# Si570_USB.net
KiCad netlist of a schematic drawn in EAGLE
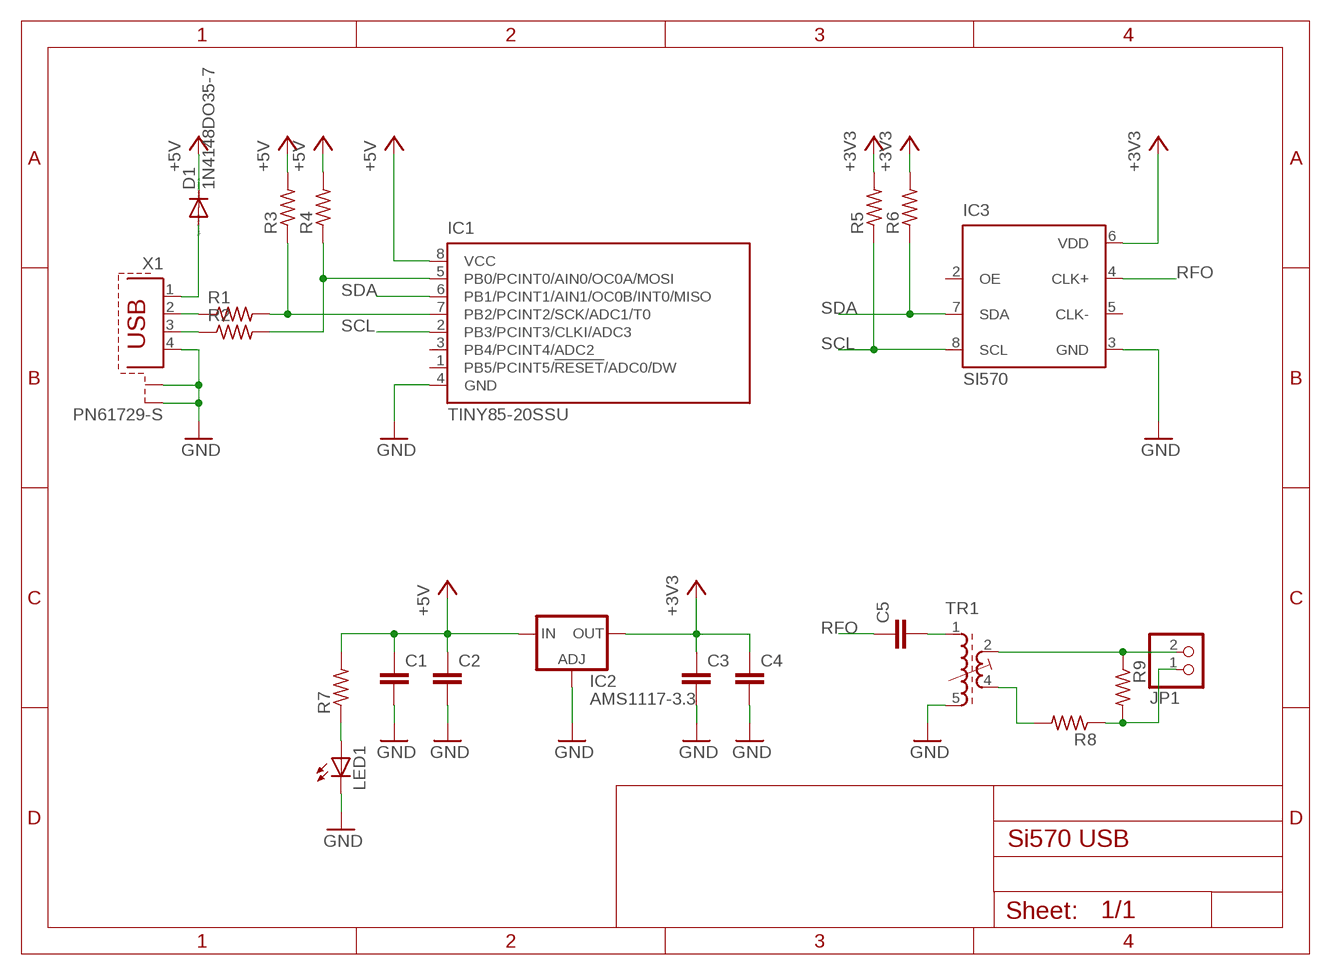
[diagram p0: schematic, sheet 1]

(export (version "E")
  (design (tool "Eeschema 10.0.6"))
  (components
    (comp (ref "C1")
      (value "C-EUC1206K")
      (footprint "eagle-import:C1206K")
      (libsource (lib "eagle-import") (part "C-EUC1206K"))
    )
    (comp (ref "C2")
      (value "C-EUC1206K")
      (footprint "eagle-import:C1206K")
      (libsource (lib "eagle-import") (part "C-EUC1206K"))
    )
    (comp (ref "C3")
      (value "C-EUC1206K")
      (footprint "eagle-import:C1206K")
      (libsource (lib "eagle-import") (part "C-EUC1206K"))
    )
    (comp (ref "C4")
      (value "C-EUC1206K")
      (footprint "eagle-import:C1206K")
      (libsource (lib "eagle-import") (part "C-EUC1206K"))
    )
    (comp (ref "C5")
      (value "C-EUC1206K")
      (footprint "eagle-import:C1206K")
      (libsource (lib "eagle-import") (part "C-EUC1206K"))
    )
    (comp (ref "D1")
      (value "1N4148DO35-7")
      (footprint "eagle-import:DO35-7")
      (libsource (lib "eagle-import") (part "1N4148DO35-7"))
    )
    (comp (ref "IC1")
      (value "TINY85-20SSU")
      (footprint "eagle-import:8S1")
      (fields (field (name "MPN") "ATTINY13-20SSU"))
      (libsource (lib "eagle-import") (part "TINY13SSU-20"))
    )
    (comp (ref "IC2")
      (value "AMS1117-3.3")
      (footprint "eagle-import:SOT223")
      (libsource (lib "eagle-import") (part "LD117A?S33TR"))
    )
    (comp (ref "IC3")
      (value "SI570")
      (footprint "eagle-import:8-PIN")
      (libsource (lib "eagle-import") (part "SI570"))
    )
    (comp (ref "JP1")
      (value "PINHD-1X2")
      (footprint "eagle-import:1X02")
      (libsource (lib "eagle-import") (part "PINHD-1X2"))
    )
    (comp (ref "LED1")
      (value "LED3MM")
      (footprint "eagle-import:LED3MM")
      (libsource (lib "eagle-import") (part "LED3MM"))
    )
    (comp (ref "R1")
      (value "R-US_R1206")
      (footprint "eagle-import:R1206")
      (libsource (lib "eagle-import") (part "R-US_R1206"))
    )
    (comp (ref "R2")
      (value "R-US_R1206")
      (footprint "eagle-import:R1206")
      (libsource (lib "eagle-import") (part "R-US_R1206"))
    )
    (comp (ref "R3")
      (value "R-US_R1206")
      (footprint "eagle-import:R1206")
      (libsource (lib "eagle-import") (part "R-US_R1206"))
    )
    (comp (ref "R4")
      (value "R-US_R1206")
      (footprint "eagle-import:R1206")
      (libsource (lib "eagle-import") (part "R-US_R1206"))
    )
    (comp (ref "R5")
      (value "R-US_R1206")
      (footprint "eagle-import:R1206")
      (libsource (lib "eagle-import") (part "R-US_R1206"))
    )
    (comp (ref "R6")
      (value "R-US_R1206")
      (footprint "eagle-import:R1206")
      (libsource (lib "eagle-import") (part "R-US_R1206"))
    )
    (comp (ref "R7")
      (value "R-US_R1206")
      (footprint "eagle-import:R1206")
      (libsource (lib "eagle-import") (part "R-US_R1206"))
    )
    (comp (ref "R8")
      (value "R-US_R1206")
      (footprint "eagle-import:R1206")
      (libsource (lib "eagle-import") (part "R-US_R1206"))
    )
    (comp (ref "R9")
      (value "R-US_R1206")
      (footprint "eagle-import:R1206")
      (libsource (lib "eagle-import") (part "R-US_R1206"))
    )
    (comp (ref "TR1")
      (value "71-4-1542")
      (footprint "eagle-import:71-5")
      (libsource (lib "eagle-import") (part "71-4-1542"))
    )
    (comp (ref "X1")
      (value "PN61729-S")
      (footprint "eagle-import:PN61729-S")
      (libsource (lib "eagle-import") (part "PN61729-S"))
    )
  )
  (nets
    (net (code "1") (name "+3V3") (class "Default")
      (node (ref "C3") (pin "1") (pinfunction "1_1") (pintype "passive"))
      (node (ref "C4") (pin "1") (pinfunction "1_1") (pintype "passive"))
      (node (ref "IC2") (pin "4") (pinfunction "OUT_4") (pintype "passive"))
      (node (ref "IC3") (pin "6") (pinfunction "VDD_6") (pintype "power_in"))
      (node (ref "R5") (pin "2") (pinfunction "2_2") (pintype "passive"))
      (node (ref "R6") (pin "2") (pinfunction "2_2") (pintype "passive"))
    )
    (net (code "2") (name "+5V") (class "Default")
      (node (ref "C1") (pin "1") (pinfunction "1_1") (pintype "passive"))
      (node (ref "C2") (pin "1") (pinfunction "1_1") (pintype "passive"))
      (node (ref "D1") (pin "C") (pinfunction "C_C") (pintype "passive"))
      (node (ref "IC1") (pin "8") (pinfunction "VCC_8") (pintype "power_in"))
      (node (ref "IC2") (pin "3") (pinfunction "IN_3") (pintype "input"))
      (node (ref "R3") (pin "2") (pinfunction "2_2") (pintype "passive"))
      (node (ref "R4") (pin "2") (pinfunction "2_2") (pintype "passive"))
      (node (ref "R7") (pin "2") (pinfunction "2_2") (pintype "passive"))
    )
    (net (code "3") (name "/RFO") (class "Default")
      (node (ref "C5") (pin "1") (pinfunction "1_1") (pintype "passive"))
      (node (ref "IC3") (pin "4") (pinfunction "CLK+_4") (pintype "output"))
    )
    (net (code "4") (name "/SCL") (class "Default")
      (node (ref "IC1") (pin "2") (pinfunction "PB3/PCINT3/CLKI/ADC3_2") (pintype "bidirectional"))
      (node (ref "IC3") (pin "8") (pinfunction "SCL_8") (pintype "input"))
      (node (ref "R5") (pin "1") (pinfunction "1_1") (pintype "passive"))
    )
    (net (code "5") (name "/SDA") (class "Default")
      (node (ref "IC1") (pin "6") (pinfunction "PB1/PCINT1/AIN1/OC0B/INT0/MISO_6") (pintype "bidirectional"))
      (node (ref "IC3") (pin "7") (pinfunction "SDA_7") (pintype "input"))
      (node (ref "R6") (pin "1") (pinfunction "1_1") (pintype "passive"))
    )
    (net (code "6") (name "GND") (class "Default")
      (node (ref "C1") (pin "2") (pinfunction "2_2") (pintype "passive"))
      (node (ref "C2") (pin "2") (pinfunction "2_2") (pintype "passive"))
      (node (ref "C3") (pin "2") (pinfunction "2_2") (pintype "passive"))
      (node (ref "C4") (pin "2") (pinfunction "2_2") (pintype "passive"))
      (node (ref "IC1") (pin "4") (pinfunction "GND_4") (pintype "power_in"))
      (node (ref "IC2") (pin "1") (pinfunction "ADJ_1") (pintype "input"))
      (node (ref "IC3") (pin "3") (pinfunction "GND_3") (pintype "power_in"))
      (node (ref "LED1") (pin "K") (pinfunction "C_K") (pintype "passive"))
      (node (ref "TR1") (pin "5") (pinfunction "E1_5") (pintype "passive"))
      (node (ref "X1") (pin "4") (pinfunction "4_4") (pintype "passive"))
      (node (ref "X1") (pin "S1") (pinfunction "S1_S1") (pintype "passive"))
      (node (ref "X1") (pin "S2") (pinfunction "S2_S2") (pintype "passive"))
    )
    (net (code "7") (name "Net-(D1-PadA)") (class "Default")
      (node (ref "D1") (pin "A") (pinfunction "A_A") (pintype "passive"))
      (node (ref "X1") (pin "1") (pinfunction "1_1") (pintype "passive"))
    )
    (net (code "8") (name "Net-(IC1-PB0{slash}PCINT0{slash}AIN0{slash}OC0A{slash}MOSI)") (class "Default")
      (node (ref "IC1") (pin "5") (pinfunction "PB0/PCINT0/AIN0/OC0A/MOSI_5") (pintype "bidirectional"))
      (node (ref "R2") (pin "2") (pinfunction "2_2") (pintype "passive"))
      (node (ref "R4") (pin "1") (pinfunction "1_1") (pintype "passive"))
    )
    (net (code "9") (name "Net-(IC1-PB2{slash}PCINT2{slash}SCK{slash}ADC1{slash}T0)") (class "Default")
      (node (ref "IC1") (pin "7") (pinfunction "PB2/PCINT2/SCK/ADC1/T0_7") (pintype "bidirectional"))
      (node (ref "R1") (pin "2") (pinfunction "2_2") (pintype "passive"))
      (node (ref "R3") (pin "1") (pinfunction "1_1") (pintype "passive"))
    )
    (net (code "10") (name "Net-(JP1-Pad1)") (class "Default")
      (node (ref "JP1") (pin "1") (pinfunction "1_1") (pintype "passive"))
      (node (ref "R8") (pin "1") (pinfunction "1_1") (pintype "passive"))
      (node (ref "R9") (pin "2") (pinfunction "2_2") (pintype "passive"))
    )
    (net (code "11") (name "Net-(LED1-PadA)") (class "Default")
      (node (ref "LED1") (pin "A") (pinfunction "A_A") (pintype "passive"))
      (node (ref "R7") (pin "1") (pinfunction "1_1") (pintype "passive"))
    )
    (net (code "12") (name "Net-(R1-Pad1)") (class "Default")
      (node (ref "R1") (pin "1") (pinfunction "1_1") (pintype "passive"))
      (node (ref "X1") (pin "2") (pinfunction "2_2") (pintype "passive"))
    )
    (net (code "13") (name "Net-(R2-Pad1)") (class "Default")
      (node (ref "R2") (pin "1") (pinfunction "1_1") (pintype "passive"))
      (node (ref "X1") (pin "3") (pinfunction "3_3") (pintype "passive"))
    )
    (net (code "14") (name "Net-(TR1A-A1)") (class "Default")
      (node (ref "C5") (pin "2") (pinfunction "2_2") (pintype "passive"))
      (node (ref "TR1") (pin "1") (pinfunction "A1_1") (pintype "passive"))
    )
    (net (code "15") (name "Net-(TR1A-A2)") (class "Default")
      (node (ref "JP1") (pin "2") (pinfunction "2_2") (pintype "passive"))
      (node (ref "R9") (pin "1") (pinfunction "1_1") (pintype "passive"))
      (node (ref "TR1") (pin "2") (pinfunction "A2_2") (pintype "passive"))
    )
    (net (code "16") (name "Net-(TR1A-E2)") (class "Default")
      (node (ref "R8") (pin "2") (pinfunction "2_2") (pintype "passive"))
      (node (ref "TR1") (pin "4") (pinfunction "E2_4") (pintype "passive"))
    )
    (net (code "17") (name "unconnected-(IC1-PB4{slash}PCINT4{slash}ADC2-Pad3)") (class "Default")
      (node (ref "IC1") (pin "3") (pinfunction "PB4/PCINT4/ADC2_3") (pintype "bidirectional"))
    )
    (net (code "18") (name "unconnected-(IC1-PB5{slash}PCINT5{slash}~{RESET}{slash}ADC0{slash}DW-Pad1)") (class "Default")
      (node (ref "IC1") (pin "1") (pinfunction "PB5/PCINT5/~{RESET}/ADC0/DW_1") (pintype "bidirectional"))
    )
    (net (code "19") (name "unconnected-(IC3-CLK--Pad5)") (class "Default")
      (node (ref "IC3") (pin "5") (pinfunction "CLK-_5") (pintype "output"))
    )
    (net (code "20") (name "unconnected-(IC3-OE-Pad2)") (class "Default")
      (node (ref "IC3") (pin "2") (pinfunction "OE_2") (pintype "input"))
    )
  )
)
